# MaiChe.net
KiCad netlist of a schematic drawn in Altium Designer
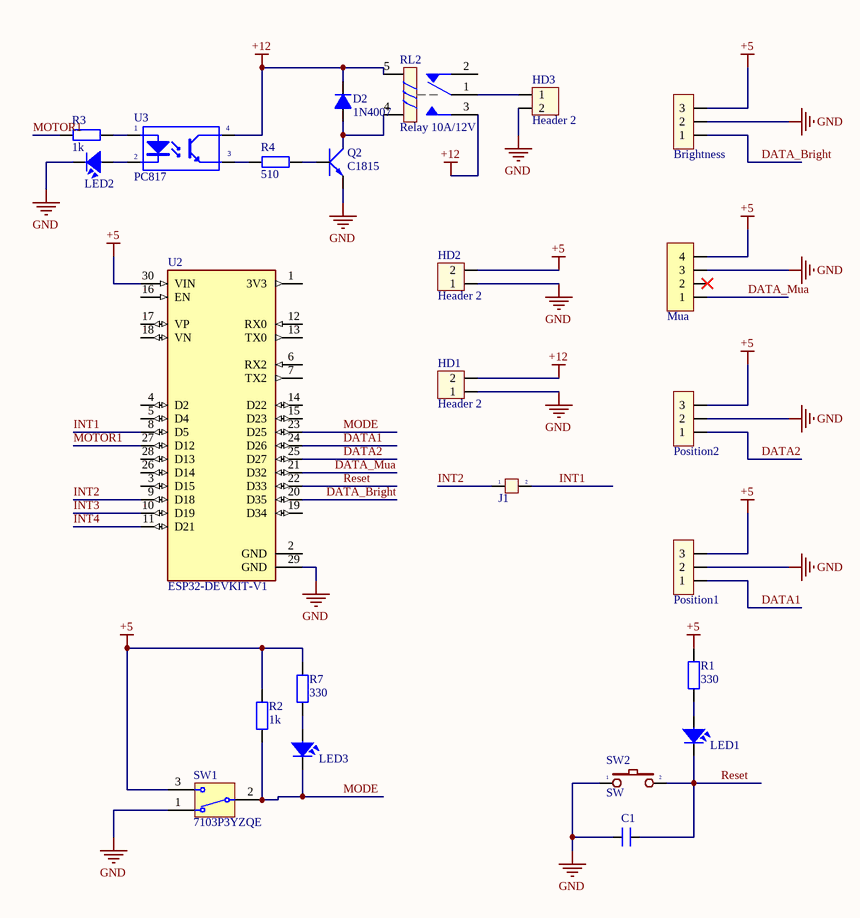
[diagram p0: MaiChe.SchDoc]

(export (version "E")
  (design (tool "Eeschema 10.0.6"))
  (components
    (comp (ref "Brightness")
      (value "Jumper 3")
      (footprint "JP3")
      (libsource (lib "syhaunguyen") (part "JP3"))
    )
    (comp (ref "C1")
      (value "100pF")
      (footprint "CN1")
      (description "Cap np  1pF - 472pF")
      (libsource (lib "syhaunguyen") (part "CN1"))
    )
    (comp (ref "D2")
      (value "1N4007")
      (footprint "D1A")
      (description "Diode 1A")
      (libsource (lib "syhaunguyen") (part "D1A"))
    )
    (comp (ref "HD1")
      (value "Header 2")
      (footprint "HED2")
      (description "Header 2 (Green)")
      (libsource (lib "") (part "Hed2_1"))
    )
    (comp (ref "HD2")
      (value "Header 2")
      (footprint "HED2")
      (description "Header 2 (Green)")
      (libsource (lib "") (part "Hed2_1"))
    )
    (comp (ref "HD3")
      (value "Header 2")
      (footprint "HED2")
      (description "Header 2 (Green)")
      (libsource (lib "syhaunguyen") (part "Hed2"))
    )
    (comp (ref "J1") (value "Jumper 2") (footprint "jp2h") (libsource (lib "syhaunguyen") (part "JP 2")))
    (comp (ref "LED1")
      (value "LED")
      (footprint "LED-3MM-YELLOW")
      (description "LED Single colour Green and Red")
      (libsource (lib "TechMT.VN_Lib_Project v2") (part "LED"))
    )
    (comp (ref "LED2")
      (value "LED")
      (footprint "LED-3MM-YELLOW")
      (description "LED Single colour Green and Red")
      (libsource (lib "TechMT.VN_Lib_Project v2") (part "LED"))
    )
    (comp (ref "LED3")
      (value "LED")
      (footprint "LED-3MM-YELLOW")
      (description "LED Single colour Green and Red")
      (libsource (lib "TechMT.VN_Lib_Project v2") (part "LED"))
    )
    (comp (ref "Mua")
      (value "JP 1x4 2.54")
      (footprint "JP 1x4 CC")
      (description "Cắm")
      (libsource (lib "Altium_Lib_by_KhueNguyenCreator") (part "JP 1x4 2.54 Cai Cong"))
    )
    (comp (ref "Position1") (value "Jumper 3") (footprint "JP3") (libsource (lib "syhaunguyen") (part "JP3")))
    (comp (ref "Position2") (value "Jumper 3") (footprint "JP3") (libsource (lib "syhaunguyen") (part "JP3")))
    (comp (ref "Q2")
      (value "C1815")
      (footprint "QTO-92")
      (description "NPN 600mW, ECB")
      (libsource (lib "syhaunguyen") (part "C1815"))
    )
    (comp (ref "R1")
      (value "330")
      (footprint "R1/4W")
      (description "Resistor 1/4W")
      (libsource (lib "syhaunguyen") (part "R1/4W"))
    )
    (comp (ref "R2")
      (value "1k")
      (footprint "R1/4W")
      (description "Resistor 1/4W")
      (libsource (lib "syhaunguyen") (part "R1/4W"))
    )
    (comp (ref "R3")
      (value "1k")
      (footprint "R1/4W")
      (description "Resistor 1/4W")
      (libsource (lib "syhaunguyen") (part "R1/4W"))
    )
    (comp (ref "R4")
      (value "510")
      (footprint "R1/4W")
      (description "Resistor 1/4W")
      (libsource (lib "syhaunguyen") (part "R1/4W"))
    )
    (comp (ref "R7")
      (value "330")
      (footprint "R1/4W")
      (description "Resistor 1/4W")
      (libsource (lib "syhaunguyen") (part "R1/4W"))
    )
    (comp (ref "RL2")
      (value "Relay 10A/12V")
      (footprint "RL_SPDT_10A")
      (description "Relay SPDT,10A - 12VDC 5 Pin")
      (libsource (lib "syhaunguyen") (part "Relay 1"))
    )
    (comp (ref "SW1")
      (value "7103P3YZQE")
      (footprint "SW_TOGGLE_7103P3YZQE")
      (description "SWITCH TOGGLE SPDT 5A 120V")
      (fields (field (name "MANUFACTURER") "C&K"))
      (libsource (lib "KhanhBK_SCH_Lib_6") (part "SW_TOGGLE_7103P3YZQE"))
    )
    (comp (ref "SW2")
      (value "SW")
      (footprint "SW2")
      (description "Switch button 2 pin")
      (libsource (lib "syhaunguyen") (part "SW2"))
    )
    (comp (ref "U2")
      (value "ESP32-DEVKIT-V1")
      (footprint "MODULE_ESP32_DEVKIT_V1")
      (fields (field (name "MF") "Do it"))
      (libsource (lib "ESP32-DEVKIT-V1") (part "ESP32-DEVKIT-V1"))
    )
    (comp (ref "U3")
      (value "PC817")
      (footprint "DIP4/W0.3")
      (description "Single Opto")
      (libsource (lib "syhaunguyen") (part "PC817"))
    )
  )
  (nets
    (net (code "1") (name "+5") (class "Default")
      (node (ref "Brightness") (pin "3") (pinfunction "3_3") (pintype "passive"))
      (node (ref "HD2") (pin "2") (pinfunction "2_2") (pintype "passive"))
      (node (ref "Mua") (pin "4") (pinfunction "4_4") (pintype "passive"))
      (node (ref "Position1") (pin "3") (pinfunction "3_3") (pintype "passive"))
      (node (ref "Position2") (pin "3") (pinfunction "3_3") (pintype "passive"))
      (node (ref "R1") (pin "1") (pinfunction "1_1") (pintype "passive"))
      (node (ref "R2") (pin "1") (pinfunction "1_1") (pintype "passive"))
      (node (ref "R7") (pin "1") (pinfunction "1_1") (pintype "passive"))
      (node (ref "SW1") (pin "3") (pinfunction "NO_3") (pintype "passive"))
      (node (ref "U2") (pin "30") (pinfunction "VIN_30") (pintype "input"))
    )
    (net (code "2") (name "+12") (class "Default")
      (node (ref "D2") (pin "2") (pinfunction "K_2") (pintype "passive"))
      (node (ref "HD1") (pin "2") (pinfunction "2_2") (pintype "passive"))
      (node (ref "RL2") (pin "3") (pinfunction "3_3") (pintype "passive"))
      (node (ref "RL2") (pin "5") (pinfunction "5_5") (pintype "passive"))
      (node (ref "U3") (pin "4") (pinfunction "C_4") (pintype "passive"))
    )
    (net (code "3") (name "/DATA1") (class "Default")
      (node (ref "Position1") (pin "1") (pinfunction "1_1") (pintype "passive"))
      (node (ref "U2") (pin "24") (pinfunction "D26_24") (pintype "bidirectional"))
    )
    (net (code "4") (name "/DATA2") (class "Default")
      (node (ref "Position2") (pin "1") (pinfunction "1_1") (pintype "passive"))
      (node (ref "U2") (pin "25") (pinfunction "D27_25") (pintype "bidirectional"))
    )
    (net (code "5") (name "/DATA_Bright") (class "Default")
      (node (ref "Brightness") (pin "1") (pinfunction "1_1") (pintype "passive"))
      (node (ref "U2") (pin "20") (pinfunction "D35_20") (pintype "bidirectional"))
    )
    (net (code "6") (name "/DATA_Mua") (class "Default")
      (node (ref "Mua") (pin "1") (pinfunction "1_1") (pintype "passive"))
      (node (ref "U2") (pin "21") (pinfunction "D32_21") (pintype "bidirectional"))
    )
    (net (code "7") (name "/INT1") (class "Default")
      (node (ref "J1") (pin "2") (pinfunction "2_2") (pintype "passive"))
      (node (ref "U2") (pin "8") (pinfunction "D5_8") (pintype "bidirectional"))
    )
    (net (code "8") (name "/INT2") (class "Default")
      (node (ref "J1") (pin "1") (pinfunction "1_1") (pintype "passive"))
      (node (ref "U2") (pin "9") (pinfunction "D18_9") (pintype "bidirectional"))
    )
    (net (code "9") (name "/INT3") (class "Default")
      (node (ref "U2") (pin "10") (pinfunction "D19_10") (pintype "bidirectional"))
    )
    (net (code "10") (name "/INT4") (class "Default")
      (node (ref "U2") (pin "11") (pinfunction "D21_11") (pintype "bidirectional"))
    )
    (net (code "11") (name "/MODE") (class "Default")
      (node (ref "LED3") (pin "2") (pinfunction "2_2") (pintype "passive"))
      (node (ref "R2") (pin "2") (pinfunction "2_2") (pintype "passive"))
      (node (ref "SW1") (pin "2") (pinfunction "COM_2") (pintype "passive"))
      (node (ref "U2") (pin "23") (pinfunction "D25_23") (pintype "bidirectional"))
    )
    (net (code "12") (name "/MOTOR1") (class "Default")
      (node (ref "R3") (pin "2") (pinfunction "2_2") (pintype "passive"))
      (node (ref "U2") (pin "27") (pinfunction "D12_27") (pintype "bidirectional"))
    )
    (net (code "13") (name "/Reset") (class "Default")
      (node (ref "C1") (pin "2") (pinfunction "2_2") (pintype "passive"))
      (node (ref "LED1") (pin "2") (pinfunction "2_2") (pintype "passive"))
      (node (ref "SW2") (pin "2") (pinfunction "2_2") (pintype "passive"))
      (node (ref "U2") (pin "22") (pinfunction "D33_22") (pintype "bidirectional"))
    )
    (net (code "14") (name "GND") (class "Default")
      (node (ref "Brightness") (pin "2") (pinfunction "2_2") (pintype "passive"))
      (node (ref "C1") (pin "1") (pinfunction "1_1") (pintype "passive"))
      (node (ref "HD1") (pin "1") (pinfunction "1_1") (pintype "passive"))
      (node (ref "HD2") (pin "1") (pinfunction "1_1") (pintype "passive"))
      (node (ref "HD3") (pin "2") (pinfunction "2_2") (pintype "passive"))
      (node (ref "LED2") (pin "2") (pinfunction "2_2") (pintype "passive"))
      (node (ref "Mua") (pin "3") (pinfunction "3_3") (pintype "passive"))
      (node (ref "Position1") (pin "2") (pinfunction "2_2") (pintype "passive"))
      (node (ref "Position2") (pin "2") (pinfunction "2_2") (pintype "passive"))
      (node (ref "Q2") (pin "1") (pinfunction "E_1") (pintype "passive"))
      (node (ref "SW1") (pin "1") (pinfunction "NC_1") (pintype "passive"))
      (node (ref "SW2") (pin "1") (pinfunction "1_1") (pintype "passive"))
      (node (ref "U2") (pin "29") (pinfunction "GND_29") (pintype "power_in"))
    )
    (net (code "15") (name "Net-(D2-A)") (class "Default")
      (node (ref "D2") (pin "1") (pinfunction "A_1") (pintype "passive"))
      (node (ref "Q2") (pin "2") (pinfunction "C_2") (pintype "passive"))
      (node (ref "RL2") (pin "4") (pinfunction "4_4") (pintype "passive"))
    )
    (net (code "16") (name "Net-(HD3-Pad1)") (class "Default")
      (node (ref "HD3") (pin "1") (pinfunction "1_1") (pintype "passive"))
      (node (ref "RL2") (pin "1") (pinfunction "1_1") (pintype "passive"))
    )
    (net (code "17") (name "Net-(LED1-Pad1)") (class "Default")
      (node (ref "LED1") (pin "1") (pinfunction "1_1") (pintype "passive"))
      (node (ref "R1") (pin "2") (pinfunction "2_2") (pintype "passive"))
    )
    (net (code "18") (name "Net-(LED3-Pad1)") (class "Default")
      (node (ref "LED3") (pin "1") (pinfunction "1_1") (pintype "passive"))
      (node (ref "R7") (pin "2") (pinfunction "2_2") (pintype "passive"))
    )
    (net (code "19") (name "Net-(Q2-B)") (class "Default")
      (node (ref "Q2") (pin "3") (pinfunction "B_3") (pintype "passive"))
      (node (ref "R4") (pin "1") (pinfunction "1_1") (pintype "passive"))
    )
    (net (code "20") (name "Net-(U3-A)") (class "Default")
      (node (ref "R3") (pin "1") (pinfunction "1_1") (pintype "passive"))
      (node (ref "U3") (pin "1") (pinfunction "A_1") (pintype "passive"))
    )
    (net (code "21") (name "Net-(U3-E)") (class "Default")
      (node (ref "R4") (pin "2") (pinfunction "2_2") (pintype "passive"))
      (node (ref "U3") (pin "3") (pinfunction "E_3") (pintype "passive"))
    )
    (net (code "22") (name "Net-(U3-K)") (class "Default")
      (node (ref "LED2") (pin "1") (pinfunction "1_1") (pintype "passive"))
      (node (ref "U3") (pin "2") (pinfunction "K_2") (pintype "passive"))
    )
    (net (code "23") (name "unconnected-(Mua-Pad2)") (class "Default")
      (node (ref "Mua") (pin "2") (pinfunction "2_2") (pintype "passive+no_connect"))
    )
    (net (code "24") (name "unconnected-(RL2-Pad2)") (class "Default")
      (node (ref "RL2") (pin "2") (pinfunction "2_2") (pintype "passive"))
    )
    (net (code "25") (name "unconnected-(U2-3V3-Pad1)") (class "Default")
      (node (ref "U2") (pin "1") (pinfunction "3V3_1") (pintype "output"))
    )
    (net (code "26") (name "unconnected-(U2-D2-Pad4)") (class "Default")
      (node (ref "U2") (pin "4") (pinfunction "D2_4") (pintype "bidirectional"))
    )
    (net (code "27") (name "unconnected-(U2-D4-Pad5)") (class "Default")
      (node (ref "U2") (pin "5") (pinfunction "D4_5") (pintype "bidirectional"))
    )
    (net (code "28") (name "unconnected-(U2-D13-Pad28)") (class "Default")
      (node (ref "U2") (pin "28") (pinfunction "D13_28") (pintype "bidirectional"))
    )
    (net (code "29") (name "unconnected-(U2-D14-Pad26)") (class "Default")
      (node (ref "U2") (pin "26") (pinfunction "D14_26") (pintype "bidirectional"))
    )
    (net (code "30") (name "unconnected-(U2-D15-Pad3)") (class "Default")
      (node (ref "U2") (pin "3") (pinfunction "D15_3") (pintype "bidirectional"))
    )
    (net (code "31") (name "unconnected-(U2-D22-Pad14)") (class "Default")
      (node (ref "U2") (pin "14") (pinfunction "D22_14") (pintype "bidirectional"))
    )
    (net (code "32") (name "unconnected-(U2-D23-Pad15)") (class "Default")
      (node (ref "U2") (pin "15") (pinfunction "D23_15") (pintype "bidirectional"))
    )
    (net (code "33") (name "unconnected-(U2-D34-Pad19)") (class "Default")
      (node (ref "U2") (pin "19") (pinfunction "D34_19") (pintype "bidirectional"))
    )
    (net (code "34") (name "unconnected-(U2-EN-Pad16)") (class "Default")
      (node (ref "U2") (pin "16") (pinfunction "EN_16") (pintype "input"))
    )
    (net (code "35") (name "unconnected-(U2-GND-Pad2)") (class "Default")
      (node (ref "U2") (pin "2") (pinfunction "GND_2") (pintype "power_in"))
    )
    (net (code "36") (name "unconnected-(U2-RX0-Pad12)") (class "Default")
      (node (ref "U2") (pin "12") (pinfunction "RX0_12") (pintype "input"))
    )
    (net (code "37") (name "unconnected-(U2-RX2-Pad6)") (class "Default")
      (node (ref "U2") (pin "6") (pinfunction "RX2_6") (pintype "input"))
    )
    (net (code "38") (name "unconnected-(U2-TX0-Pad13)") (class "Default")
      (node (ref "U2") (pin "13") (pinfunction "TX0_13") (pintype "output"))
    )
    (net (code "39") (name "unconnected-(U2-TX2-Pad7)") (class "Default")
      (node (ref "U2") (pin "7") (pinfunction "TX2_7") (pintype "output"))
    )
    (net (code "40") (name "unconnected-(U2-VN-Pad18)") (class "Default")
      (node (ref "U2") (pin "18") (pinfunction "VN_18") (pintype "bidirectional"))
    )
    (net (code "41") (name "unconnected-(U2-VP-Pad17)") (class "Default")
      (node (ref "U2") (pin "17") (pinfunction "VP_17") (pintype "bidirectional"))
    )
  )
)
